# DB10005_TopLevel.net
KiCad netlist of a schematic drawn in Altium Designer
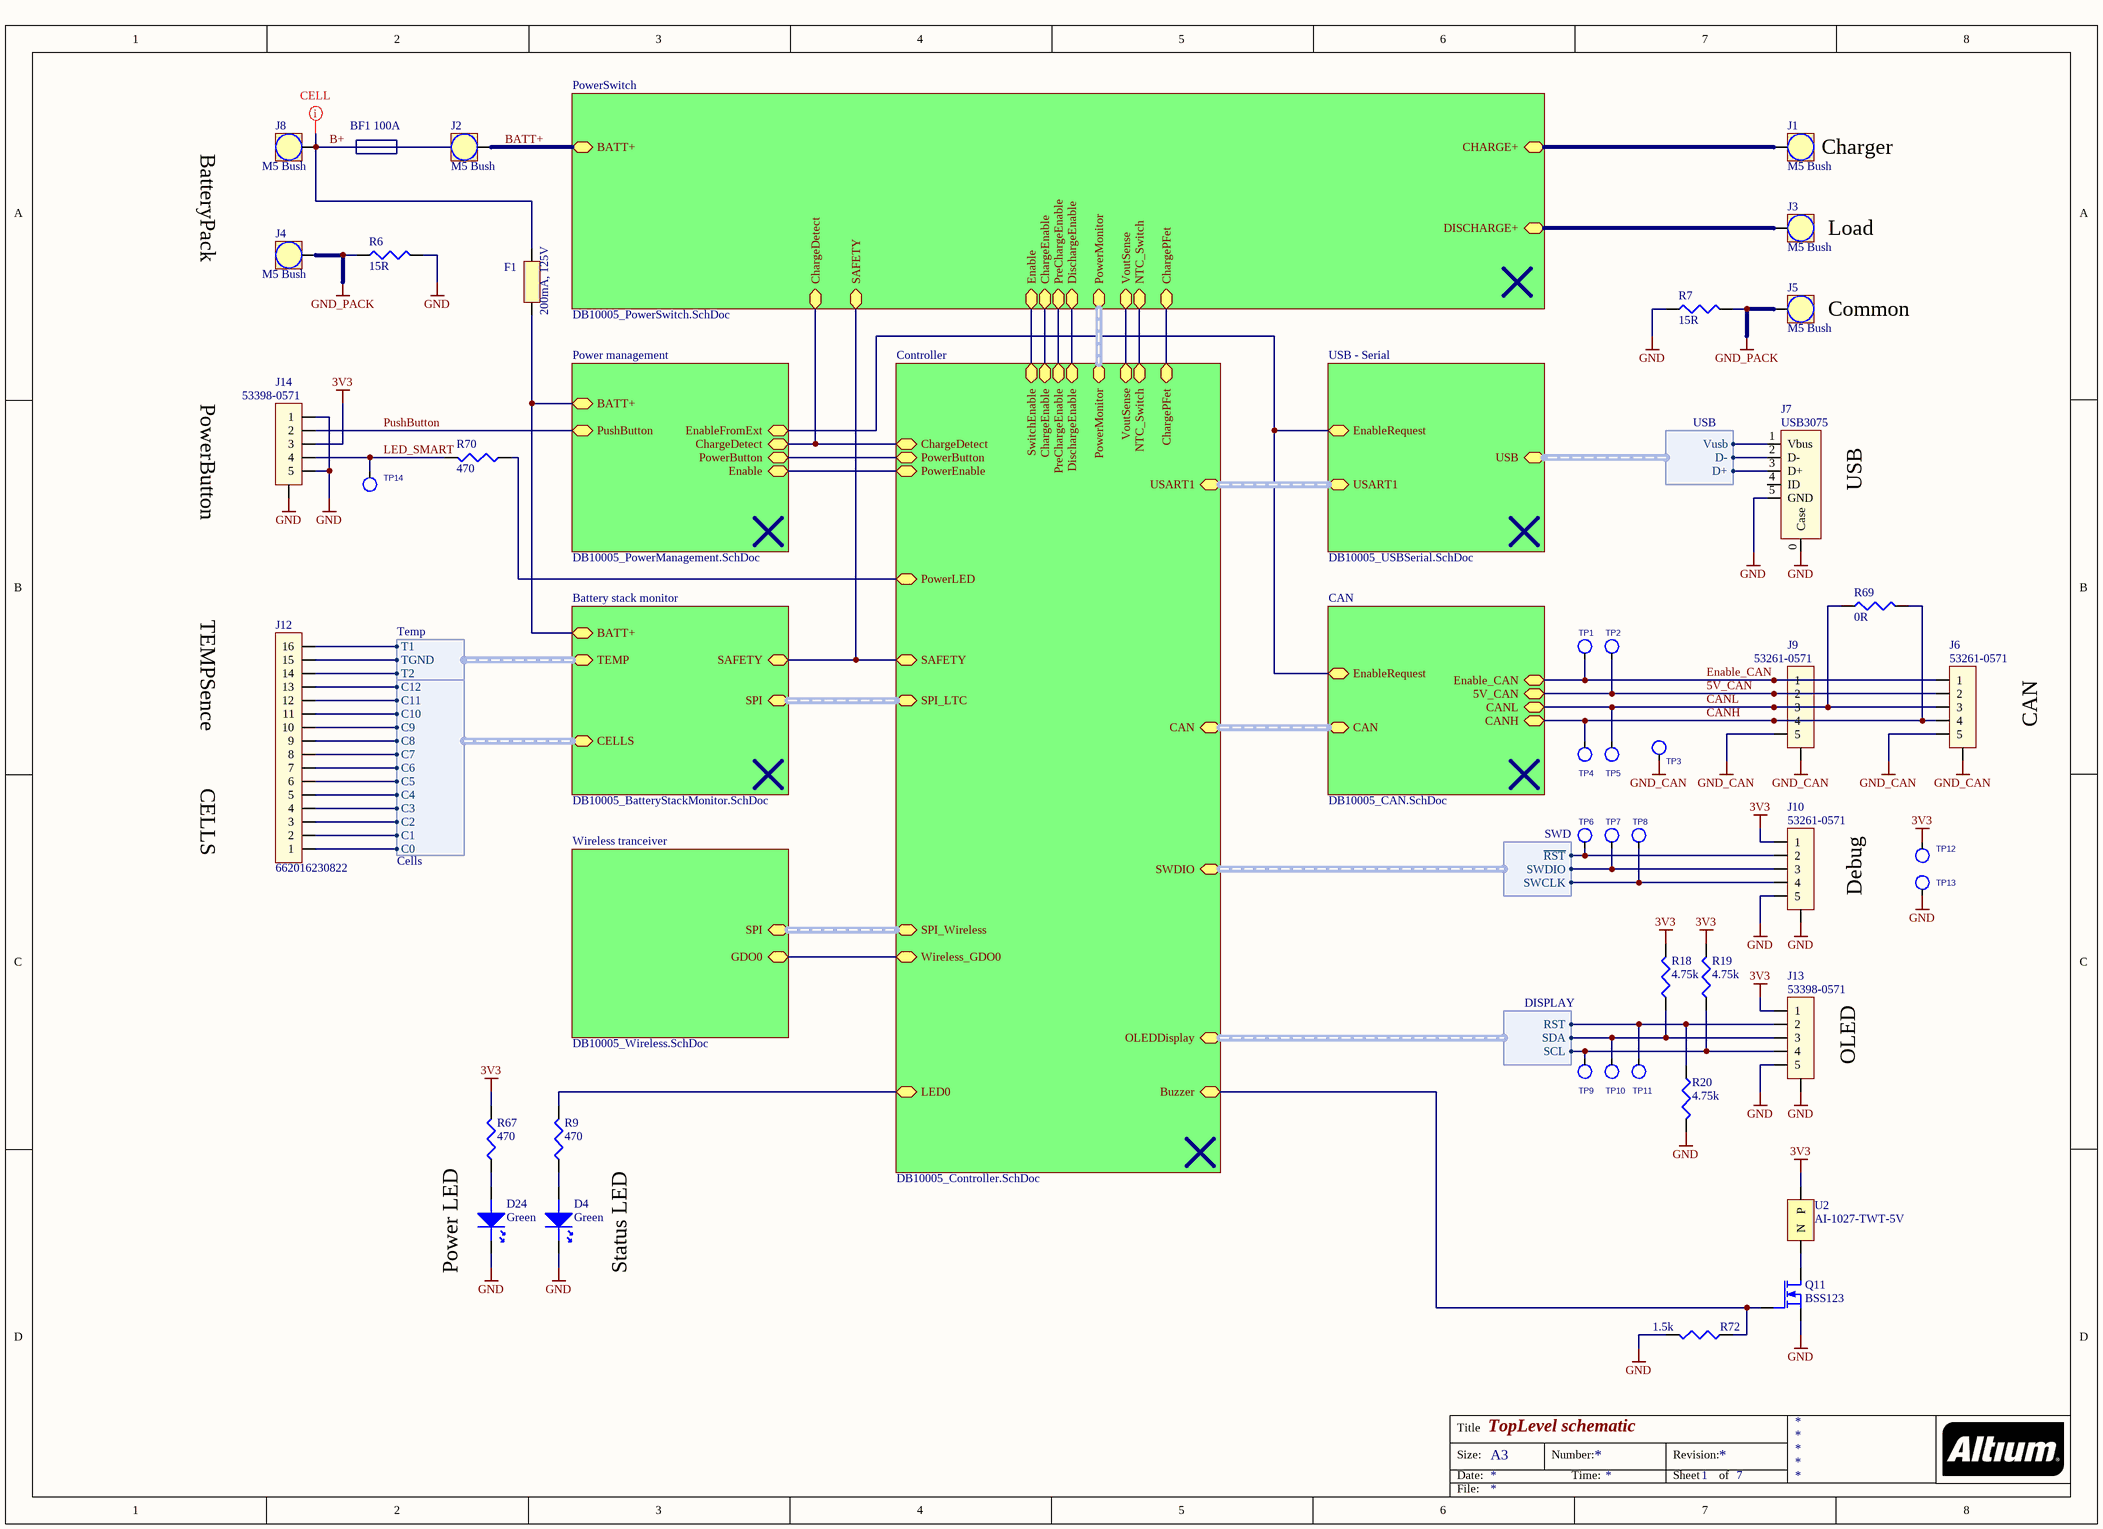
[diagram p0: DB10005_TopLevel.SchDoc]

(export (version "E")
  (design (tool "Eeschema 10.0.6"))
  (components
    (comp (ref "D4")
      (value "Green")
      (footprint "D-0805")
      (description "Led, Green, Li:12mcd, Vf:2.2V, If:0.02A")
      (libsource (lib "AR_Misc") (part "KP-2012SGC"))
    )
    (comp (ref "D24")
      (value "Green")
      (footprint "D-0805")
      (description "Led, Green, Li:12mcd, Vf:2.2V, If:0.02A")
      (libsource (lib "AR_Misc") (part "KP-2012SGC"))
    )
    (comp (ref "F1")
      (value "200mA, 125V")
      (footprint "F1206")
      (description "Fuse, Slow Blow, 200 mA, 125 VAC, 125 VDC")
      (libsource (lib "AR_Misc") (part "0466.200NR"))
    )
    (comp (ref "J1")
      (value "M5 Bush")
      (footprint "7460408_HAL Surface")
      (description "Bush with Circumference M5")
      (libsource (lib "AR_Connectors") (part "7460408"))
    )
    (comp (ref "J2")
      (value "M5 Bush")
      (footprint "7460408_HAL Surface")
      (description "Bush with Circumference M5")
      (libsource (lib "") (part "7460408_1"))
    )
    (comp (ref "J3")
      (value "M5 Bush")
      (footprint "7460408_HAL Surface")
      (description "Bush with Circumference M5")
      (libsource (lib "AR_Connectors") (part "7460408"))
    )
    (comp (ref "J4")
      (value "M5 Bush")
      (footprint "7460408_HAL Surface")
      (description "Bush with Circumference M5")
      (libsource (lib "") (part "7460408_1"))
    )
    (comp (ref "J5")
      (value "M5 Bush")
      (footprint "7460408_HAL Surface")
      (description "Bush with Circumference M5")
      (libsource (lib "") (part "7460408_2"))
    )
    (comp (ref "J6")
      (value "53261-0571")
      (footprint "53261-0571")
      (description "PicoBlade 53261 Series, 5Pin, Right Angle")
      (libsource (lib "AR_Connectors") (part "53261-0571"))
    )
    (comp (ref "J7")
      (value "USB3075")
      (footprint "USB3075 - NOSLOT")
      (description "USB 2.0 MICRO B, RCPT, 5POS, SMT")
      (libsource (lib "AR_Connectors") (part "USB3075"))
    )
    (comp (ref "J8")
      (value "M5 Bush")
      (footprint "7460408_HAL Surface")
      (description "Bush with Circumference M5")
      (libsource (lib "") (part "7460408_1"))
    )
    (comp (ref "J9")
      (value "53261-0571")
      (footprint "53261-0571")
      (description "PicoBlade 53261 Series, 5Pin, Right Angle")
      (libsource (lib "AR_Connectors") (part "53261-0571"))
    )
    (comp (ref "J10")
      (value "53261-0571")
      (footprint "53261-0571")
      (description "PicoBlade 53261 Series, 5Pin, Right Angle")
      (libsource (lib "AR_Connectors") (part "53261-0571"))
    )
    (comp (ref "J12")
      (value "662016230822")
      (footprint "662016230822")
      (description "WR-MPC3 Series, Surface Mount, Header, 16 Contacts, 3 mm")
      (libsource (lib "AR_Connectors") (part "662016230822"))
    )
    (comp (ref "J13")
      (value "53398-0571")
      (footprint "53398-0571")
      (description "PicoBlade 53398 Series, 5Pin, Right Angle")
      (libsource (lib "") (part "53398-0571_1"))
    )
    (comp (ref "J14")
      (value "53398-0571")
      (footprint "53398-0571")
      (description "PicoBlade 53398 Series, 5Pin, Right Angle")
      (libsource (lib "AR_Connectors") (part "53398-0571"))
    )
    (comp (ref "Q11")
      (value "BSS123")
      (footprint "SOT-23")
      (description "Mosfet, N-channel, Vds:100V, Id:0.15A, Vgs-th:2.8V, Rds-on:3.5ohm")
      (libsource (lib "AR_Mosfets") (part "BSS123"))
    )
    (comp (ref "R6")
      (value "15R")
      (footprint "2512")
      (description "Resistor, 15R, 1%, 2W, 200V, 200PPM, 2512")
      (libsource (lib "AR_Resistors_SMD") (part "15/2512/2W/250V"))
    )
    (comp (ref "R7")
      (value "15R")
      (footprint "2512")
      (description "Resistor, 15R, 1%, 2W, 200V, 200PPM, 2512")
      (libsource (lib "AR_Resistors_SMD") (part "15/2512/2W/250V"))
    )
    (comp (ref "R9")
      (value "470")
      (footprint "0402")
      (description "Resistor, 470, 1%, 0.0625W, 50V, 100PPM, 0402")
      (libsource (lib "AR_Resistors_SMD") (part "470/0402/0063W/50V"))
    )
    (comp (ref "R18")
      (value "4.75k")
      (footprint "0402")
      (description "Resistor, 4.75k, 0.1%, 0.0625W, 50V, 100PPM, 0402")
      (libsource (lib "AR_Resistors_SMD") (part "4.75k/0402/0063W/50V"))
    )
    (comp (ref "R19")
      (value "4.75k")
      (footprint "0402")
      (description "Resistor, 4.75k, 0.1%, 0.0625W, 50V, 100PPM, 0402")
      (libsource (lib "AR_Resistors_SMD") (part "4.75k/0402/0063W/50V"))
    )
    (comp (ref "R20")
      (value "4.75k")
      (footprint "0402")
      (description "Resistor, 4.75k, 0.1%, 0.0625W, 50V, 100PPM, 0402")
      (libsource (lib "AR_Resistors_SMD") (part "4.75k/0402/0063W/50V"))
    )
    (comp (ref "R67")
      (value "470")
      (footprint "0402")
      (description "Resistor, 470, 1%, 0.0625W, 50V, 100PPM, 0402")
      (libsource (lib "AR_Resistors_SMD") (part "470/0402/0063W/50V"))
    )
    (comp (ref "R69")
      (value "0R")
      (footprint "0805")
      (description "Resistor, 0R, 0.1%, 0.1W, 150V, 200PPM, 0805")
      (libsource (lib "AR_Resistors_SMD") (part "0/0805/0100W/150V"))
    )
    (comp (ref "R70")
      (value "470")
      (footprint "0402")
      (description "Resistor, 470, 1%, 0.0625W, 50V, 100PPM, 0402")
      (libsource (lib "AR_Resistors_SMD") (part "470/0402/0063W/50V"))
    )
    (comp (ref "R72")
      (value "1.5k")
      (footprint "0402")
      (description "Resistor, 1.5k, 0.1%, 0.0625W, 50V, 100PPM, 0402")
      (libsource (lib "AR_Resistors_SMD") (part "1.5k/0402/0063W/50V"))
    )
    (comp (ref "TP1")
      (value "1.3TP")
      (footprint "TP2-1.3MM")
      (description "1.3mm")
      (libsource (lib "AR_Misc") (part "TESTPT4"))
    )
    (comp (ref "TP2")
      (value "1.3TP")
      (footprint "TP2-1.3MM")
      (description "1.3mm")
      (libsource (lib "AR_Misc") (part "TESTPT4"))
    )
    (comp (ref "TP3")
      (value "1.3TP")
      (footprint "TP2-1.3MM")
      (description "1.3mm")
      (libsource (lib "AR_Misc") (part "TESTPT4"))
    )
    (comp (ref "TP4")
      (value "1.3TP")
      (footprint "TP2-1.3MM")
      (description "1.3mm")
      (libsource (lib "AR_Misc") (part "TESTPT4"))
    )
    (comp (ref "TP5")
      (value "1.3TP")
      (footprint "TP2-1.3MM")
      (description "1.3mm")
      (libsource (lib "AR_Misc") (part "TESTPT4"))
    )
    (comp (ref "TP6")
      (value "1.3TP")
      (footprint "TP2-1.3MM")
      (description "1.3mm")
      (libsource (lib "AR_Misc") (part "TESTPT4"))
    )
    (comp (ref "TP7")
      (value "1.3TP")
      (footprint "TP2-1.3MM")
      (description "1.3mm")
      (libsource (lib "AR_Misc") (part "TESTPT4"))
    )
    (comp (ref "TP8")
      (value "1.3TP")
      (footprint "TP2-1.3MM")
      (description "1.3mm")
      (libsource (lib "AR_Misc") (part "TESTPT4"))
    )
    (comp (ref "TP9")
      (value "1.3TP")
      (footprint "TP2-1.3MM")
      (description "1.3mm")
      (libsource (lib "AR_Misc") (part "TESTPT4"))
    )
    (comp (ref "TP10")
      (value "1.3TP")
      (footprint "TP2-1.3MM")
      (description "1.3mm")
      (libsource (lib "AR_Misc") (part "TESTPT4"))
    )
    (comp (ref "TP11")
      (value "1.3TP")
      (footprint "TP2-1.3MM")
      (description "1.3mm")
      (libsource (lib "AR_Misc") (part "TESTPT4"))
    )
    (comp (ref "TP12")
      (value "1.3TP")
      (footprint "TP2-1.3MM")
      (description "1.3mm")
      (libsource (lib "AR_Misc") (part "TESTPT4"))
    )
    (comp (ref "TP13")
      (value "1.3TP")
      (footprint "TP2-1.3MM")
      (description "1.3mm")
      (libsource (lib "AR_Misc") (part "TESTPT4"))
    )
    (comp (ref "TP14")
      (value "1.3TP")
      (footprint "TP2-1.3MM")
      (description "1.3mm")
      (libsource (lib "AR_Misc") (part "TESTPT4"))
    )
    (comp (ref "U2")
      (value "AI-1027-TWT-5V")
      (footprint "AI-1027-TWT")
      (description "EM 5VDC 2300Hz 82dBA Continuous Top Fire")
      (libsource (lib "AR_Misc") (part "AI-1027-TWT-5V-2-R"))
    )
  )
  (nets
    (net (code "6") (name "/5V_CAN") (class "Default")
      (node (ref "J6") (pin "2") (pinfunction "2_2") (pintype "passive"))
      (node (ref "J9") (pin "2") (pinfunction "2_2") (pintype "passive"))
      (node (ref "TP2") (pin "1") (pinfunction "TP_1") (pintype "passive"))
    )
    (net (code "7") (name "/B+") (class "Default")
      (node (ref "F1") (pin "2") (pinfunction "2_2") (pintype "passive"))
      (node (ref "J8") (pin "1") (pinfunction "1_1") (pintype "passive"))
    )
    (net (code "8") (name "/BATT+") (class "Default")
      (node (ref "J2") (pin "1") (pinfunction "1_1") (pintype "passive"))
    )
    (net (code "9") (name "/BATT+_1") (class "Default")
      (node (ref "F1") (pin "1") (pinfunction "1_1") (pintype "passive"))
    )
    (net (code "10") (name "/Buzzer") (class "Default")
      (node (ref "Q11") (pin "G") (pinfunction "G_G") (pintype "passive"))
      (node (ref "R72") (pin "1") (pinfunction "1_1") (pintype "passive"))
    )
    (net (code "11") (name "/C0") (class "Default")
      (node (ref "J12") (pin "1") (pinfunction "1_1") (pintype "passive"))
    )
    (net (code "12") (name "/C1") (class "Default")
      (node (ref "J12") (pin "2") (pinfunction "2_2") (pintype "passive"))
    )
    (net (code "13") (name "/C2") (class "Default")
      (node (ref "J12") (pin "3") (pinfunction "3_3") (pintype "passive"))
    )
    (net (code "14") (name "/C3") (class "Default")
      (node (ref "J12") (pin "4") (pinfunction "4_4") (pintype "passive"))
    )
    (net (code "15") (name "/C4") (class "Default")
      (node (ref "J12") (pin "5") (pinfunction "5_5") (pintype "passive"))
    )
    (net (code "16") (name "/C5") (class "Default")
      (node (ref "J12") (pin "6") (pinfunction "6_6") (pintype "passive"))
    )
    (net (code "17") (name "/C6") (class "Default")
      (node (ref "J12") (pin "7") (pinfunction "7_7") (pintype "passive"))
    )
    (net (code "18") (name "/C7") (class "Default")
      (node (ref "J12") (pin "8") (pinfunction "8_8") (pintype "passive"))
    )
    (net (code "19") (name "/C8") (class "Default")
      (node (ref "J12") (pin "9") (pinfunction "9_9") (pintype "passive"))
    )
    (net (code "20") (name "/C9") (class "Default")
      (node (ref "J12") (pin "10") (pinfunction "10_10") (pintype "passive"))
    )
    (net (code "21") (name "/C10") (class "Default")
      (node (ref "J12") (pin "11") (pinfunction "11_11") (pintype "passive"))
    )
    (net (code "22") (name "/C11") (class "Default")
      (node (ref "J12") (pin "12") (pinfunction "12_12") (pintype "passive"))
    )
    (net (code "23") (name "/C12") (class "Default")
      (node (ref "J12") (pin "13") (pinfunction "13_13") (pintype "passive"))
    )
    (net (code "24") (name "/CANH") (class "Default")
      (node (ref "J6") (pin "4") (pinfunction "4_4") (pintype "passive"))
      (node (ref "J9") (pin "4") (pinfunction "4_4") (pintype "passive"))
      (node (ref "R69") (pin "2") (pinfunction "2_2") (pintype "passive"))
      (node (ref "TP4") (pin "1") (pinfunction "TP_1") (pintype "passive"))
    )
    (net (code "25") (name "/CANL") (class "Default")
      (node (ref "J6") (pin "3") (pinfunction "3_3") (pintype "passive"))
      (node (ref "J9") (pin "3") (pinfunction "3_3") (pintype "passive"))
      (node (ref "R69") (pin "1") (pinfunction "1_1") (pintype "passive"))
      (node (ref "TP5") (pin "1") (pinfunction "TP_1") (pintype "passive"))
    )
    (net (code "27") (name "/CHARGE+") (class "Default")
      (node (ref "J1") (pin "1") (pinfunction "1_1") (pintype "passive"))
    )
    (net (code "31") (name "/D+") (class "Default")
      (node (ref "J7") (pin "3") (pinfunction "D+_3") (pintype "passive"))
    )
    (net (code "32") (name "/D-") (class "Default")
      (node (ref "J7") (pin "2") (pinfunction "D-_2") (pintype "passive"))
    )
    (net (code "33") (name "/DISCHARGE+") (class "Default")
      (node (ref "J3") (pin "1") (pinfunction "1_1") (pintype "passive"))
    )
    (net (code "38") (name "/Enable_CAN") (class "Default")
      (node (ref "J6") (pin "1") (pinfunction "1_1") (pintype "passive"))
      (node (ref "J9") (pin "1") (pinfunction "1_1") (pintype "passive"))
      (node (ref "TP1") (pin "1") (pinfunction "TP_1") (pintype "passive"))
    )
    (net (code "40") (name "/LED0") (class "Default")
      (node (ref "R9") (pin "2") (pinfunction "2_2") (pintype "passive"))
    )
    (net (code "41") (name "/LED_SMART") (class "Default")
      (node (ref "J14") (pin "4") (pinfunction "4_4") (pintype "passive"))
      (node (ref "R70") (pin "2") (pinfunction "2_2") (pintype "passive"))
      (node (ref "TP14") (pin "1") (pinfunction "TP_1") (pintype "passive"))
    )
    (net (code "44") (name "/PowerLED") (class "Default")
      (node (ref "R70") (pin "1") (pinfunction "1_1") (pintype "passive"))
    )
    (net (code "47") (name "/PushButton") (class "Default")
      (node (ref "J14") (pin "2") (pinfunction "2_2") (pintype "passive"))
    )
    (net (code "48") (name "/RST") (class "Default")
      (node (ref "J13") (pin "2") (pinfunction "2_2") (pintype "passive"))
      (node (ref "R20") (pin "1") (pinfunction "1_1") (pintype "passive"))
      (node (ref "TP11") (pin "1") (pinfunction "TP_1") (pintype "passive"))
    )
    (net (code "50") (name "/SCL") (class "Default")
      (node (ref "J13") (pin "4") (pinfunction "4_4") (pintype "passive"))
      (node (ref "R19") (pin "1") (pinfunction "1_1") (pintype "passive"))
      (node (ref "TP9") (pin "1") (pinfunction "TP_1") (pintype "passive"))
    )
    (net (code "51") (name "/SDA") (class "Default")
      (node (ref "J13") (pin "3") (pinfunction "3_3") (pintype "passive"))
      (node (ref "R18") (pin "1") (pinfunction "1_1") (pintype "passive"))
      (node (ref "TP10") (pin "1") (pinfunction "TP_1") (pintype "passive"))
    )
    (net (code "54") (name "/SWCLK") (class "Default")
      (node (ref "J10") (pin "4") (pinfunction "4_4") (pintype "passive"))
      (node (ref "TP8") (pin "1") (pinfunction "TP_1") (pintype "passive"))
    )
    (net (code "55") (name "/SWDIO") (class "Default")
      (node (ref "J10") (pin "3") (pinfunction "3_3") (pintype "passive"))
      (node (ref "TP7") (pin "1") (pinfunction "TP_1") (pintype "passive"))
    )
    (net (code "56") (name "/T1") (class "Default")
      (node (ref "J12") (pin "16") (pinfunction "16_16") (pintype "passive"))
    )
    (net (code "57") (name "/T2") (class "Default")
      (node (ref "J12") (pin "14") (pinfunction "14_14") (pintype "passive"))
    )
    (net (code "58") (name "/TGND") (class "Default")
      (node (ref "J12") (pin "15") (pinfunction "15_15") (pintype "passive"))
    )
    (net (code "61") (name "/Vusb") (class "Default")
      (node (ref "J7") (pin "1") (pinfunction "Vbus_1") (pintype "passive"))
    )
    (net (code "67") (name "/~{RST}") (class "Default")
      (node (ref "J10") (pin "2") (pinfunction "2_2") (pintype "passive"))
      (node (ref "TP6") (pin "1") (pinfunction "TP_1") (pintype "passive"))
    )
    (net (code "68") (name "3V3") (class "Default")
      (node (ref "J10") (pin "1") (pinfunction "1_1") (pintype "passive"))
      (node (ref "J13") (pin "1") (pinfunction "1_1") (pintype "passive"))
      (node (ref "J14") (pin "3") (pinfunction "3_3") (pintype "passive"))
      (node (ref "R18") (pin "2") (pinfunction "2_2") (pintype "passive"))
      (node (ref "R19") (pin "2") (pinfunction "2_2") (pintype "passive"))
      (node (ref "R67") (pin "2") (pinfunction "2_2") (pintype "passive"))
      (node (ref "TP12") (pin "1") (pinfunction "TP_1") (pintype "passive"))
      (node (ref "U2") (pin "P") (pinfunction "P_P") (pintype "passive"))
    )
    (net (code "69") (name "GND") (class "Default")
      (node (ref "D24") (pin "K") (pinfunction "K_K") (pintype "passive"))
      (node (ref "D4") (pin "K") (pinfunction "K_K") (pintype "passive"))
      (node (ref "J10") (pin "0") (pinfunction "SHLD_0") (pintype "passive"))
      (node (ref "J10") (pin "5") (pinfunction "5_5") (pintype "passive"))
      (node (ref "J13") (pin "0") (pinfunction "SHLD_0") (pintype "passive"))
      (node (ref "J13") (pin "5") (pinfunction "5_5") (pintype "passive"))
      (node (ref "J14") (pin "0") (pinfunction "SHLD_0") (pintype "passive"))
      (node (ref "J14") (pin "1") (pinfunction "1_1") (pintype "passive"))
      (node (ref "J14") (pin "5") (pinfunction "5_5") (pintype "passive"))
      (node (ref "J7") (pin "0") (pinfunction "Case_0") (pintype "passive"))
      (node (ref "J7") (pin "5") (pinfunction "GND_5") (pintype "passive"))
      (node (ref "Q11") (pin "S") (pinfunction "S_S") (pintype "passive"))
      (node (ref "R20") (pin "2") (pinfunction "2_2") (pintype "passive"))
      (node (ref "R6") (pin "2") (pinfunction "2_2") (pintype "passive"))
      (node (ref "R7") (pin "2") (pinfunction "2_2") (pintype "passive"))
      (node (ref "R72") (pin "2") (pinfunction "2_2") (pintype "passive"))
      (node (ref "TP13") (pin "1") (pinfunction "TP_1") (pintype "passive"))
    )
    (net (code "70") (name "GND_CAN") (class "Default")
      (node (ref "J6") (pin "0") (pinfunction "SHLD_0") (pintype "passive"))
      (node (ref "J6") (pin "5") (pinfunction "5_5") (pintype "passive"))
      (node (ref "J9") (pin "0") (pinfunction "SHLD_0") (pintype "passive"))
      (node (ref "J9") (pin "5") (pinfunction "5_5") (pintype "passive"))
      (node (ref "TP3") (pin "1") (pinfunction "TP_1") (pintype "passive"))
    )
    (net (code "71") (name "GND_PACK") (class "Default")
      (node (ref "J4") (pin "1") (pinfunction "1_1") (pintype "passive"))
      (node (ref "J5") (pin "1") (pinfunction "1_1") (pintype "passive"))
      (node (ref "R6") (pin "1") (pinfunction "1_1") (pintype "passive"))
      (node (ref "R7") (pin "1") (pinfunction "1_1") (pintype "passive"))
    )
    (net (code "72") (name "Net-(D4-PadA)") (class "Default")
      (node (ref "D4") (pin "A") (pinfunction "A_A") (pintype "passive"))
      (node (ref "R9") (pin "1") (pinfunction "1_1") (pintype "passive"))
    )
    (net (code "73") (name "Net-(D24-PadA)") (class "Default")
      (node (ref "D24") (pin "A") (pinfunction "A_A") (pintype "passive"))
      (node (ref "R67") (pin "1") (pinfunction "1_1") (pintype "passive"))
    )
    (net (code "74") (name "Net-(Q11-PadD)") (class "Default")
      (node (ref "Q11") (pin "D") (pinfunction "D_D") (pintype "passive"))
      (node (ref "U2") (pin "N") (pinfunction "N_N") (pintype "passive"))
    )
    (net (code "75") (name "unconnected-(J7-ID-Pad4)") (class "Default")
      (node (ref "J7") (pin "4") (pinfunction "ID_4") (pintype "passive"))
    )
  )
)
